# AC-DC.net
KiCad netlist of a schematic drawn in EAGLE
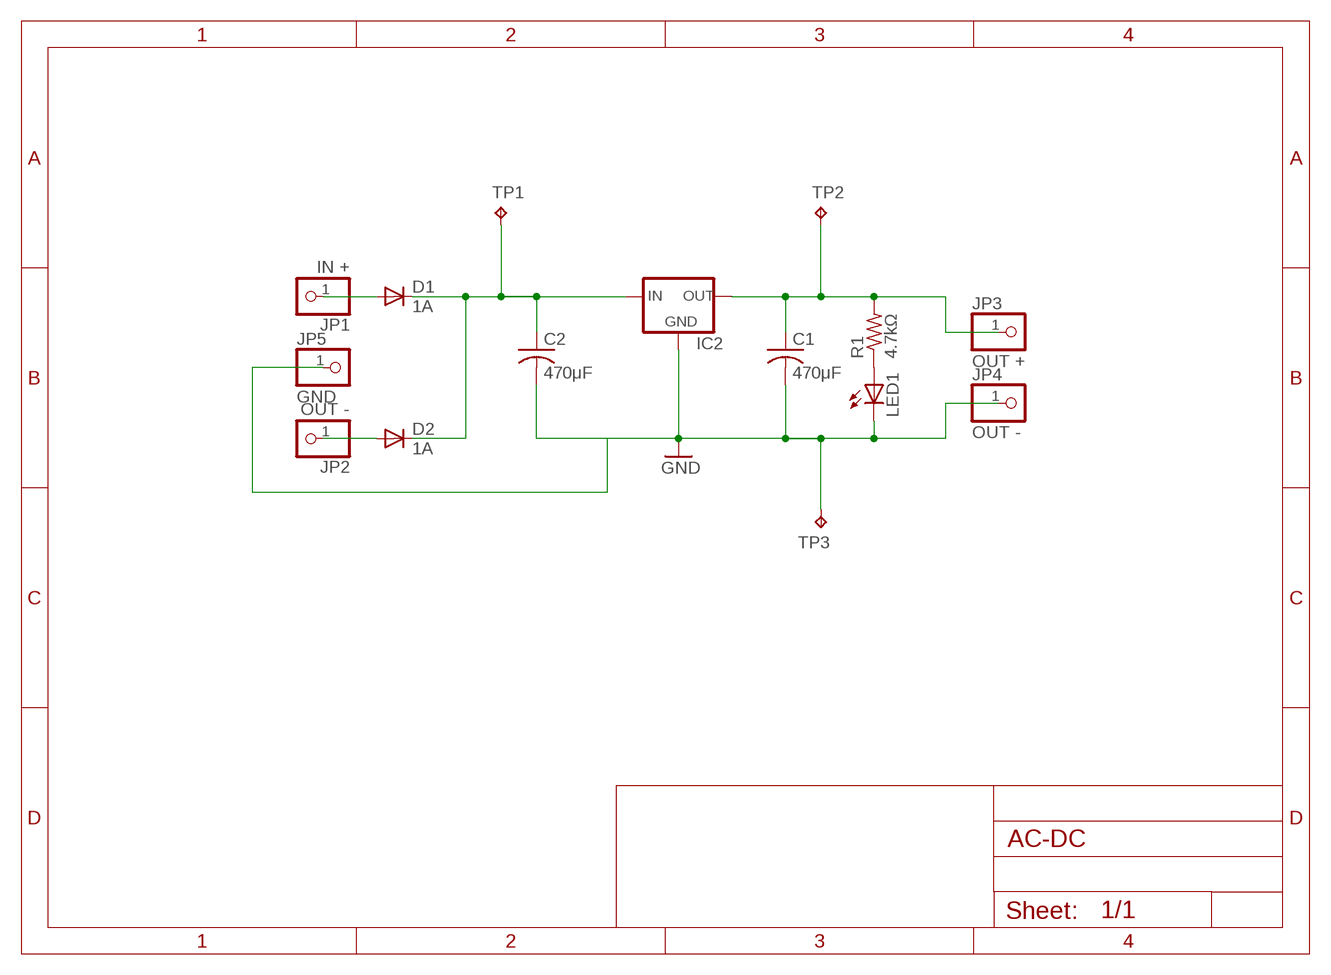
[diagram p0: schematic, sheet 1]

(export (version "E")
  (design (tool "Eeschema 10.0.6"))
  (components
    (comp (ref "C1")
      (value "470μF")
      (footprint "eagle-import:C075-032X103")
      (libsource (lib "eagle-import") (part "C-US075-032X103"))
    )
    (comp (ref "C2")
      (value "470μF")
      (footprint "eagle-import:C075-032X103")
      (libsource (lib "eagle-import") (part "C-US075-032X103"))
    )
    (comp (ref "D1")
      (value "1A")
      (footprint "eagle-import:DO41-10")
      (libsource (lib "eagle-import") (part "1N4004"))
    )
    (comp (ref "D2")
      (value "1A")
      (footprint "eagle-import:DO41-10")
      (libsource (lib "eagle-import") (part "1N4004"))
    )
    (comp (ref "IC2")
      (value "78XXS")
      (footprint "eagle-import:78XXS")
      (libsource (lib "eagle-import") (part "78XXS"))
    )
    (comp (ref "JP1")
      (value "IN +")
      (footprint "eagle-import:1X01")
      (libsource (lib "eagle-import") (part "PINHD-1X1"))
    )
    (comp (ref "JP2")
      (value "OUT -")
      (footprint "eagle-import:1X01")
      (libsource (lib "eagle-import") (part "PINHD-1X1"))
    )
    (comp (ref "JP3")
      (value "OUT +")
      (footprint "eagle-import:1X01")
      (libsource (lib "eagle-import") (part "PINHD-1X1"))
    )
    (comp (ref "JP4")
      (value "OUT -")
      (footprint "eagle-import:1X01")
      (libsource (lib "eagle-import") (part "PINHD-1X1"))
    )
    (comp (ref "JP5")
      (value "GND")
      (footprint "eagle-import:1X01")
      (libsource (lib "eagle-import") (part "PINHD-1X1"))
    )
    (comp (ref "LED1")
      (value "LED10MM")
      (footprint "eagle-import:LED10MM")
      (libsource (lib "eagle-import") (part "LED10MM"))
    )
    (comp (ref "R1")
      (value "4.7kΩ")
      (footprint "eagle-import:0207_10")
      (libsource (lib "eagle-import") (part "R-US_0207/10"))
    )
    (comp (ref "TP1")
      (value "TPB1,27")
      (footprint "eagle-import:B1,27")
      (libsource (lib "eagle-import") (part "TPB1,27"))
    )
    (comp (ref "TP2")
      (value "TPB1,27")
      (footprint "eagle-import:B1,27")
      (libsource (lib "eagle-import") (part "TPB1,27"))
    )
    (comp (ref "TP3")
      (value "TPB1,27")
      (footprint "eagle-import:B1,27")
      (libsource (lib "eagle-import") (part "TPB1,27"))
    )
  )
  (nets
    (net (code "1") (name "GND") (class "Default")
      (node (ref "C1") (pin "2") (pinfunction "2_2") (pintype "passive"))
      (node (ref "C2") (pin "2") (pinfunction "2_2") (pintype "passive"))
      (node (ref "IC2") (pin "GND") (pinfunction "GND_GND") (pintype "input"))
      (node (ref "JP4") (pin "1") (pinfunction "1_1") (pintype "passive"))
      (node (ref "JP5") (pin "1") (pinfunction "1_1") (pintype "passive"))
      (node (ref "LED1") (pin "K") (pinfunction "C_K") (pintype "passive"))
      (node (ref "TP3") (pin "TP") (pinfunction "TP_TP") (pintype "input"))
    )
    (net (code "2") (name "Net-(C1-Pad1)") (class "Default")
      (node (ref "C1") (pin "1") (pinfunction "1_1") (pintype "passive"))
      (node (ref "IC2") (pin "OUT") (pinfunction "OUT_OUT") (pintype "passive"))
      (node (ref "JP3") (pin "1") (pinfunction "1_1") (pintype "passive"))
      (node (ref "R1") (pin "2") (pinfunction "2_2") (pintype "passive"))
      (node (ref "TP2") (pin "TP") (pinfunction "TP_TP") (pintype "input"))
    )
    (net (code "3") (name "Net-(C2-Pad1)") (class "Default")
      (node (ref "C2") (pin "1") (pinfunction "1_1") (pintype "passive"))
      (node (ref "D1") (pin "C") (pinfunction "C_C") (pintype "passive"))
      (node (ref "D2") (pin "C") (pinfunction "C_C") (pintype "passive"))
      (node (ref "IC2") (pin "IN") (pinfunction "IN_IN") (pintype "input"))
      (node (ref "TP1") (pin "TP") (pinfunction "TP_TP") (pintype "input"))
    )
    (net (code "4") (name "Net-(D1-PadA)") (class "Default")
      (node (ref "D1") (pin "A") (pinfunction "A_A") (pintype "passive"))
      (node (ref "JP1") (pin "1") (pinfunction "1_1") (pintype "passive"))
    )
    (net (code "5") (name "Net-(D2-PadA)") (class "Default")
      (node (ref "D2") (pin "A") (pinfunction "A_A") (pintype "passive"))
      (node (ref "JP2") (pin "1") (pinfunction "1_1") (pintype "passive"))
    )
    (net (code "6") (name "Net-(LED1-PadA)") (class "Default")
      (node (ref "LED1") (pin "A") (pinfunction "A_A") (pintype "passive"))
      (node (ref "R1") (pin "1") (pinfunction "1_1") (pintype "passive"))
    )
  )
)
